# differential_lowpass.net
KiCad netlist of a schematic drawn in Altium Designer
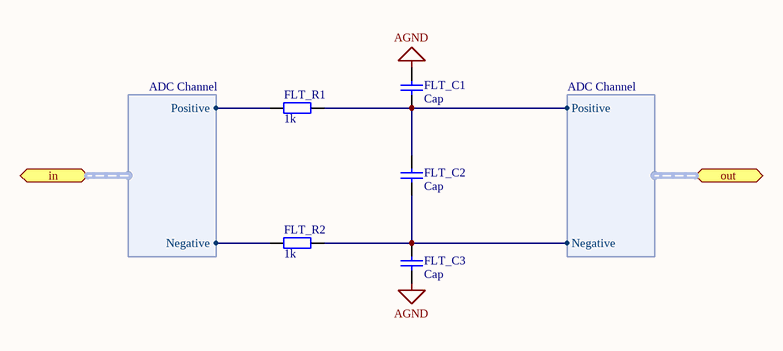
[diagram p0: differential_lowpass.SchDoc]

(export (version "E")
  (design (tool "Eeschema 10.0.6"))
  (components
    (comp (ref "FLT_C1")
      (value "Cap")
      (footprint "SMD_Capacitor_0603")
      (libsource (lib "capacitors") (part "Cap"))
    )
    (comp (ref "FLT_C2")
      (value "Cap")
      (footprint "SMD_Capacitor_0603")
      (libsource (lib "capacitors") (part "Cap"))
    )
    (comp (ref "FLT_C3")
      (value "Cap")
      (footprint "SMD_Capacitor_0603")
      (libsource (lib "capacitors") (part "Cap"))
    )
    (comp (ref "FLT_R1")
      (value "1k")
      (footprint "SMD_Resistor_0603")
      (libsource (lib "resistors") (part "Res"))
    )
    (comp (ref "FLT_R2")
      (value "1k")
      (footprint "SMD_Resistor_0603")
      (libsource (lib "resistors") (part "Res"))
    )
  )
  (nets
    (net (code "4") (name "AGND") (class "Default")
      (node (ref "FLT_C1") (pin "1") (pinfunction "1_1") (pintype "passive"))
      (node (ref "FLT_C3") (pin "2") (pinfunction "2_2") (pintype "passive"))
    )
    (net (code "5") (name "Net-(FLT_C1-Pad2)") (class "Default")
      (node (ref "FLT_C1") (pin "2") (pinfunction "2_2") (pintype "passive"))
      (node (ref "FLT_C2") (pin "1") (pinfunction "1_1") (pintype "passive"))
      (node (ref "FLT_R1") (pin "2") (pinfunction "2_2") (pintype "passive"))
    )
    (net (code "6") (name "Net-(FLT_C2-Pad2)") (class "Default")
      (node (ref "FLT_C2") (pin "2") (pinfunction "2_2") (pintype "passive"))
      (node (ref "FLT_C3") (pin "1") (pinfunction "1_1") (pintype "passive"))
      (node (ref "FLT_R2") (pin "2") (pinfunction "2_2") (pintype "passive"))
    )
    (net (code "7") (name "unconnected-(FLT_R1-Pad1)") (class "Default")
      (node (ref "FLT_R1") (pin "1") (pinfunction "1_1") (pintype "passive"))
    )
    (net (code "8") (name "unconnected-(FLT_R2-Pad1)") (class "Default")
      (node (ref "FLT_R2") (pin "1") (pinfunction "1_1") (pintype "passive"))
    )
  )
)
